# SCH_TempMate_1.net
KiCad netlist of a schematic drawn in EasyEDA
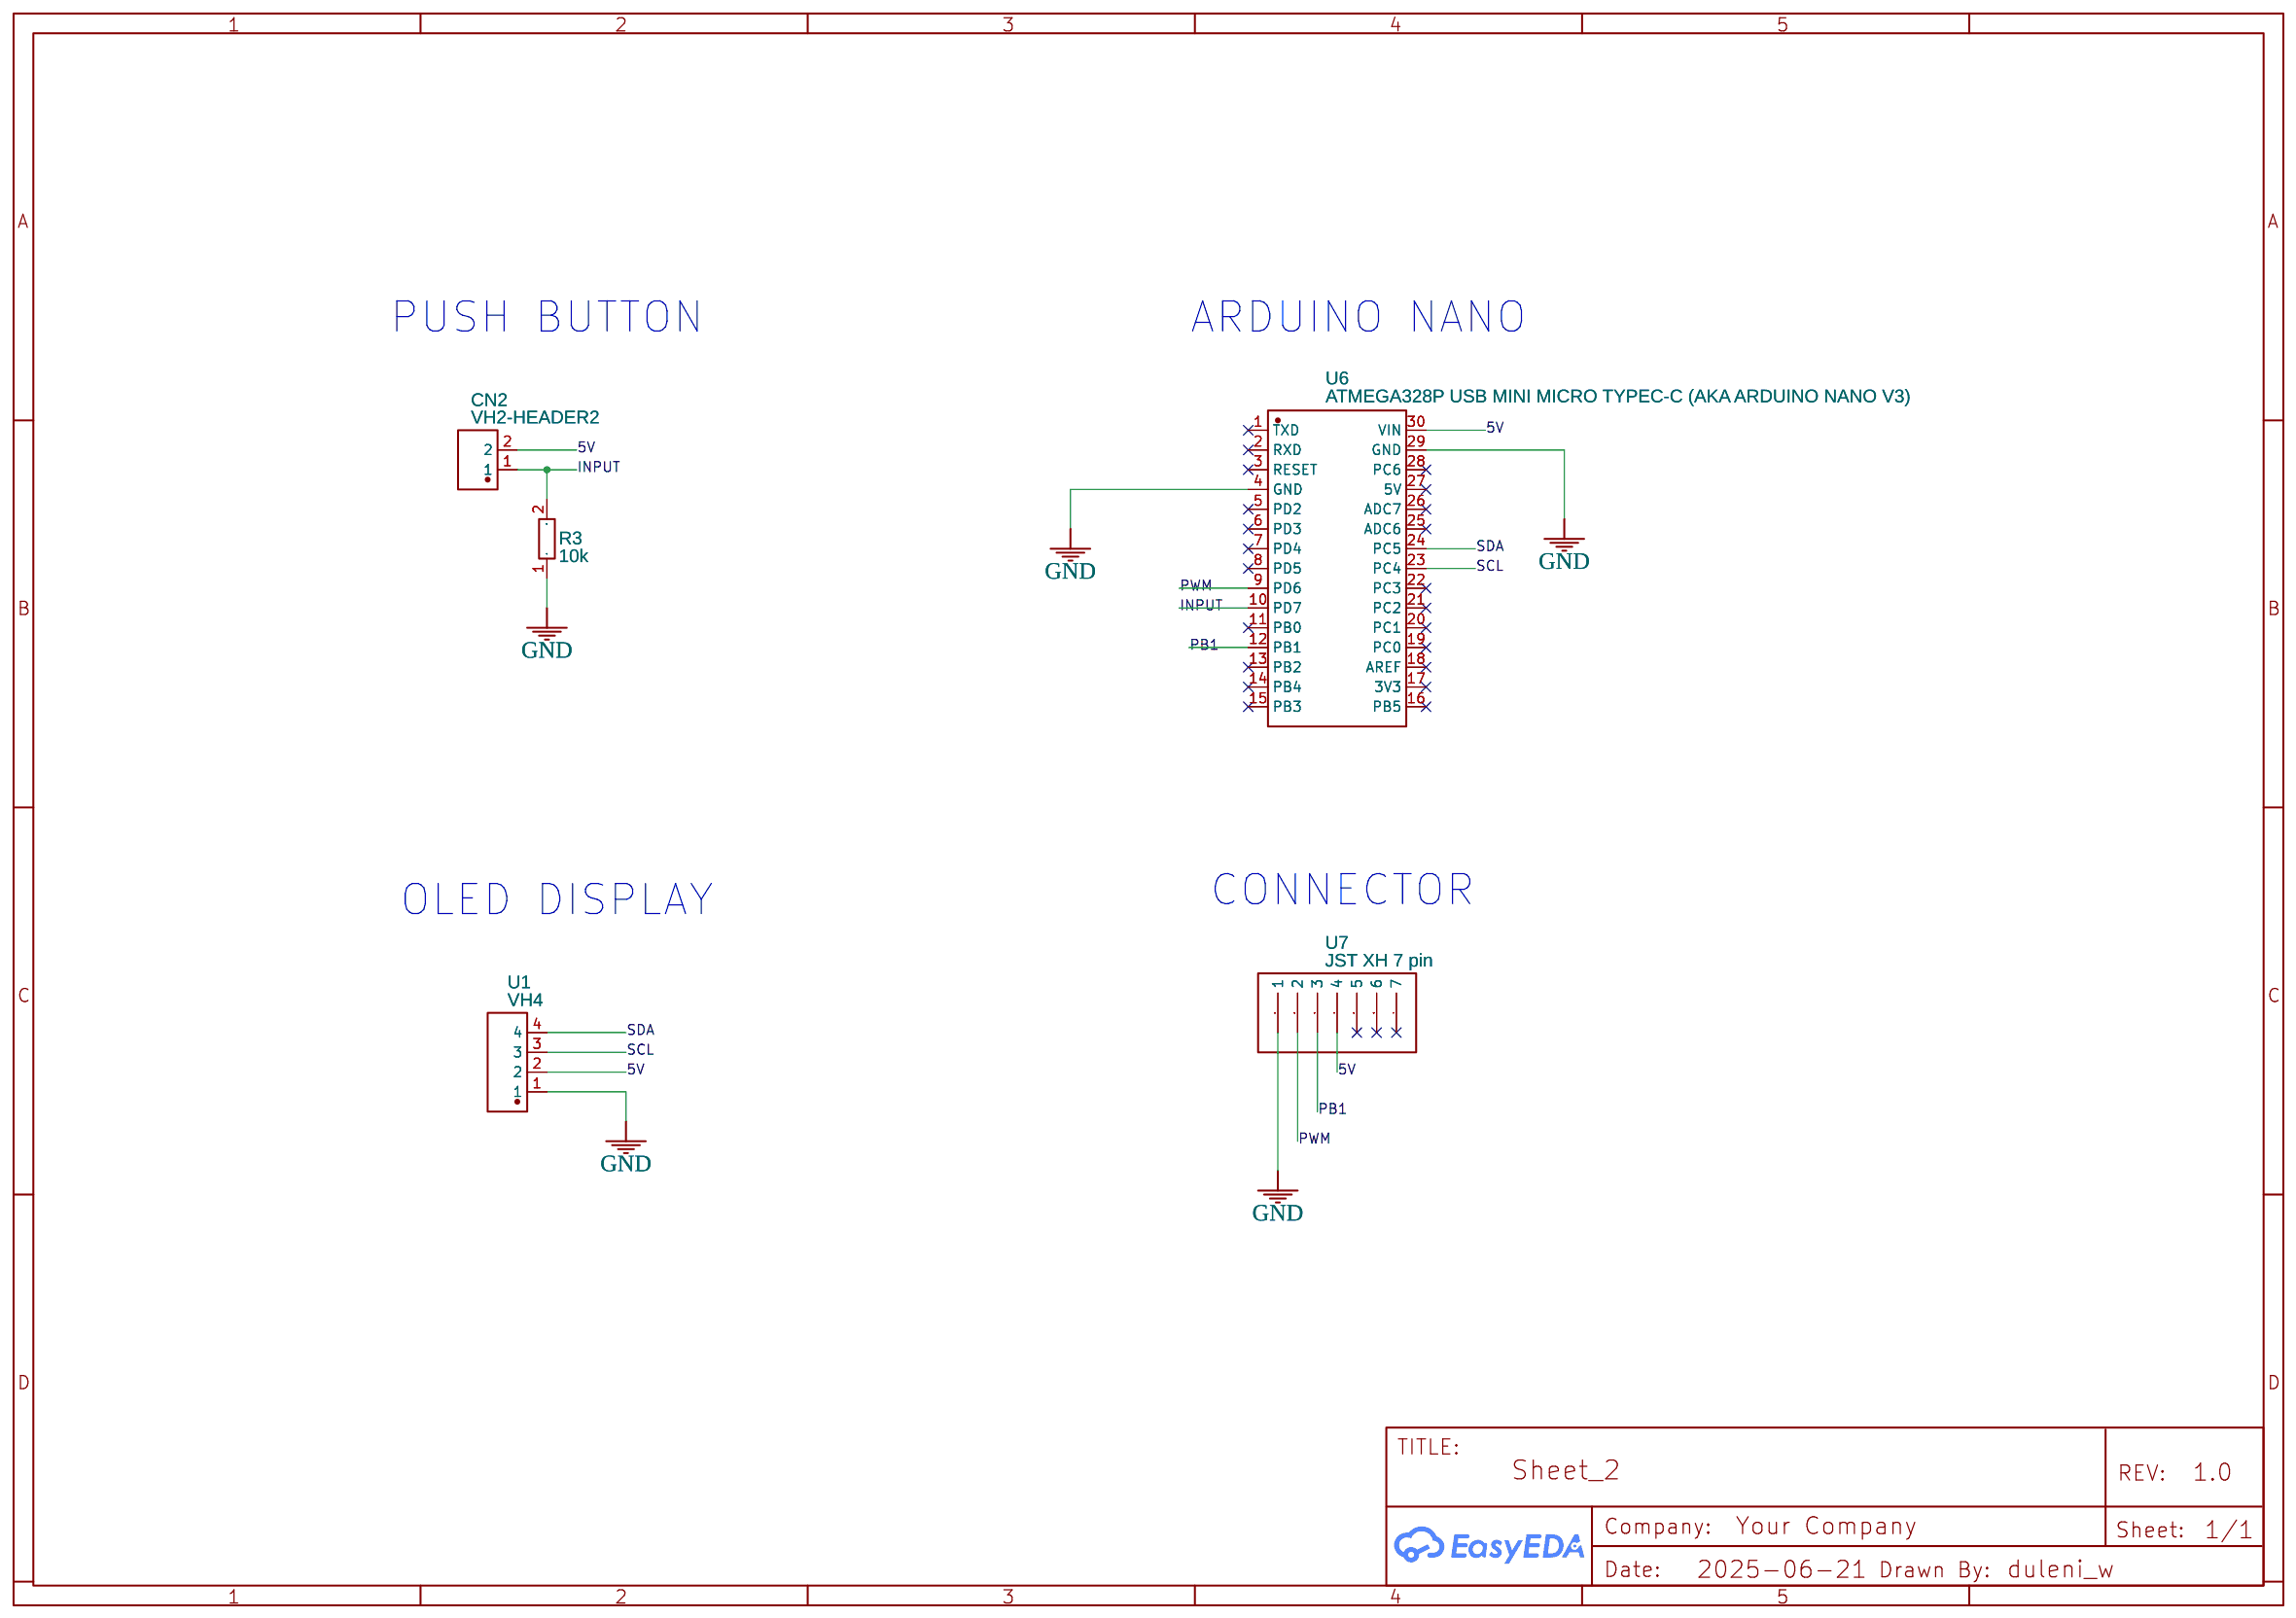
[diagram p0: schematic sheet]

(export (version "E")
  (design (tool "Eeschema 10.0.6"))
  (components
    (comp (ref "CN2")
      (value "VH2-HEADER2")
      (fields (field (name "Manufacturer Part") "VH2-Header2"))
      (libsource (lib "") (part "VH2-HEADER2"))
    )
    (comp (ref "R3")
      (value "10k")
      (fields (field (name "Manufacturer Part") "MF1/4W-330Ω±1% T") (field (name "Manufacturer") "CCO(千志电子)"))
      (libsource (lib "") (part "XOHM-THROUGH-HOLE-RESISTORS-5%-1/4W-D2.3-L6.5MM"))
    )
    (comp (ref "U1") (value "VH4") (libsource (lib "") (part "VH4")))
    (comp (ref "U6")
      (value "ATMEGA328P USB MINI MICRO TYPEC-C (AKA ARDUINO NANO V3)")
      (fields (field (name "Manufacturer Part") "ATMEGA328P USB Mini Micro Typec-C (aka Arduino Nano V3)"))
      (libsource (lib "") (part "ATMEGA328P USB MINI MICRO TYPEC-C (AKA ARDUINO NANO V3)"))
    )
    (comp (ref "U7") (value "JST XH 7 pin") (libsource (lib "") (part "JST XH 7 pin")))
  )
  (nets
    (net (code "1") (name "/5V") (class "Default")
      (node (ref "CN2") (pin "2") (pinfunction "2_2") (pintype "unspecified"))
      (node (ref "U1") (pin "2") (pinfunction "2_2") (pintype "unspecified"))
      (node (ref "U6") (pin "30") (pinfunction "VIN_30") (pintype "unspecified"))
      (node (ref "U7") (pin "4") (pinfunction "4_4") (pintype "unspecified"))
    )
    (net (code "2") (name "/INPUT") (class "Default")
      (node (ref "CN2") (pin "1") (pinfunction "1_1") (pintype "unspecified"))
      (node (ref "R3") (pin "2") (pinfunction "2_2") (pintype "unspecified"))
      (node (ref "U6") (pin "10") (pinfunction "PD7_10") (pintype "unspecified"))
    )
    (net (code "3") (name "/PB1") (class "Default")
      (node (ref "U6") (pin "12") (pinfunction "PB1_12") (pintype "unspecified"))
      (node (ref "U7") (pin "3") (pinfunction "3_3") (pintype "unspecified"))
    )
    (net (code "4") (name "/PWM") (class "Default")
      (node (ref "U6") (pin "9") (pinfunction "PD6_9") (pintype "unspecified"))
      (node (ref "U7") (pin "2") (pinfunction "2_2") (pintype "unspecified"))
    )
    (net (code "5") (name "/SCL") (class "Default")
      (node (ref "U1") (pin "3") (pinfunction "3_3") (pintype "unspecified"))
      (node (ref "U6") (pin "23") (pinfunction "PC4_23") (pintype "unspecified"))
    )
    (net (code "6") (name "/SDA") (class "Default")
      (node (ref "U1") (pin "4") (pinfunction "4_4") (pintype "unspecified"))
      (node (ref "U6") (pin "24") (pinfunction "PC5_24") (pintype "unspecified"))
    )
    (net (code "7") (name "GND") (class "Default")
      (node (ref "R3") (pin "1") (pinfunction "1_1") (pintype "unspecified"))
      (node (ref "U1") (pin "1") (pinfunction "1_1") (pintype "unspecified"))
      (node (ref "U6") (pin "29") (pinfunction "GND_29") (pintype "unspecified"))
      (node (ref "U6") (pin "4") (pinfunction "GND_4") (pintype "unspecified"))
      (node (ref "U7") (pin "1") (pinfunction "1_1") (pintype "unspecified"))
    )
    (net (code "8") (name "unconnected-(U6-3V3-Pad17)") (class "Default")
      (node (ref "U6") (pin "17") (pinfunction "3V3_17") (pintype "unspecified+no_connect"))
    )
    (net (code "9") (name "unconnected-(U6-5V-Pad27)") (class "Default")
      (node (ref "U6") (pin "27") (pinfunction "5V_27") (pintype "unspecified+no_connect"))
    )
    (net (code "10") (name "unconnected-(U6-ADC6-Pad25)") (class "Default")
      (node (ref "U6") (pin "25") (pinfunction "ADC6_25") (pintype "unspecified+no_connect"))
    )
    (net (code "11") (name "unconnected-(U6-ADC7-Pad26)") (class "Default")
      (node (ref "U6") (pin "26") (pinfunction "ADC7_26") (pintype "unspecified+no_connect"))
    )
    (net (code "12") (name "unconnected-(U6-AREF-Pad18)") (class "Default")
      (node (ref "U6") (pin "18") (pinfunction "AREF_18") (pintype "unspecified+no_connect"))
    )
    (net (code "13") (name "unconnected-(U6-PB0-Pad11)") (class "Default")
      (node (ref "U6") (pin "11") (pinfunction "PB0_11") (pintype "unspecified+no_connect"))
    )
    (net (code "14") (name "unconnected-(U6-PB2-Pad13)") (class "Default")
      (node (ref "U6") (pin "13") (pinfunction "PB2_13") (pintype "unspecified+no_connect"))
    )
    (net (code "15") (name "unconnected-(U6-PB3-Pad15)") (class "Default")
      (node (ref "U6") (pin "15") (pinfunction "PB3_15") (pintype "unspecified+no_connect"))
    )
    (net (code "16") (name "unconnected-(U6-PB4-Pad14)") (class "Default")
      (node (ref "U6") (pin "14") (pinfunction "PB4_14") (pintype "unspecified+no_connect"))
    )
    (net (code "17") (name "unconnected-(U6-PB5-Pad16)") (class "Default")
      (node (ref "U6") (pin "16") (pinfunction "PB5_16") (pintype "unspecified+no_connect"))
    )
    (net (code "18") (name "unconnected-(U6-PC0-Pad19)") (class "Default")
      (node (ref "U6") (pin "19") (pinfunction "PC0_19") (pintype "unspecified+no_connect"))
    )
    (net (code "19") (name "unconnected-(U6-PC1-Pad20)") (class "Default")
      (node (ref "U6") (pin "20") (pinfunction "PC1_20") (pintype "unspecified+no_connect"))
    )
    (net (code "20") (name "unconnected-(U6-PC2-Pad21)") (class "Default")
      (node (ref "U6") (pin "21") (pinfunction "PC2_21") (pintype "unspecified+no_connect"))
    )
    (net (code "21") (name "unconnected-(U6-PC3-Pad22)") (class "Default")
      (node (ref "U6") (pin "22") (pinfunction "PC3_22") (pintype "unspecified+no_connect"))
    )
    (net (code "22") (name "unconnected-(U6-PC6-Pad28)") (class "Default")
      (node (ref "U6") (pin "28") (pinfunction "PC6_28") (pintype "unspecified+no_connect"))
    )
    (net (code "23") (name "unconnected-(U6-PD2-Pad5)") (class "Default")
      (node (ref "U6") (pin "5") (pinfunction "PD2_5") (pintype "unspecified+no_connect"))
    )
    (net (code "24") (name "unconnected-(U6-PD3-Pad6)") (class "Default")
      (node (ref "U6") (pin "6") (pinfunction "PD3_6") (pintype "unspecified+no_connect"))
    )
    (net (code "25") (name "unconnected-(U6-PD4-Pad7)") (class "Default")
      (node (ref "U6") (pin "7") (pinfunction "PD4_7") (pintype "unspecified+no_connect"))
    )
    (net (code "26") (name "unconnected-(U6-PD5-Pad8)") (class "Default")
      (node (ref "U6") (pin "8") (pinfunction "PD5_8") (pintype "unspecified+no_connect"))
    )
    (net (code "27") (name "unconnected-(U6-RESET-Pad3)") (class "Default")
      (node (ref "U6") (pin "3") (pinfunction "RESET_3") (pintype "unspecified+no_connect"))
    )
    (net (code "28") (name "unconnected-(U6-RXD-Pad2)") (class "Default")
      (node (ref "U6") (pin "2") (pinfunction "RXD_2") (pintype "unspecified+no_connect"))
    )
    (net (code "29") (name "unconnected-(U6-TXD-Pad1)") (class "Default")
      (node (ref "U6") (pin "1") (pinfunction "TXD_1") (pintype "unspecified+no_connect"))
    )
    (net (code "30") (name "unconnected-(U7-Pad5)") (class "Default")
      (node (ref "U7") (pin "5") (pinfunction "5_5") (pintype "unspecified+no_connect"))
    )
    (net (code "31") (name "unconnected-(U7-Pad6)") (class "Default")
      (node (ref "U7") (pin "6") (pinfunction "6_6") (pintype "unspecified+no_connect"))
    )
    (net (code "32") (name "unconnected-(U7-Pad7)") (class "Default")
      (node (ref "U7") (pin "7") (pinfunction "7_7") (pintype "unspecified+no_connect"))
    )
  )
)
